# absensi_wemos.net
KiCad netlist of a schematic drawn in EAGLE
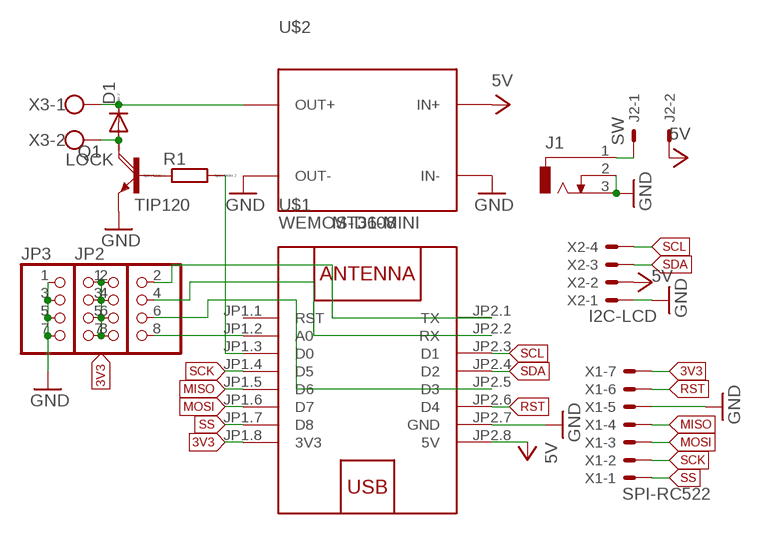
[diagram p0: schematic, sheet 1]

(export (version "E")
  (design (tool "Eeschema 10.0.6"))
  (components
    (comp (ref "D1")
      (value "DIODE-DO-214AC")
      (footprint "eagle-import:DO-214AC")
      (libsource (lib "eagle-import") (part "DIODE-DO-214AC"))
    )
    (comp (ref "J1")
      (value "DCJ0303")
      (footprint "eagle-import:DCJ0303")
      (libsource (lib "eagle-import") (part "DCJ0303"))
    )
    (comp (ref "J2")
      (value "SW")
      (footprint "eagle-import:6410-02")
      (fields (field (name "MF") "MOLEX"))
      (libsource (lib "eagle-import") (part "22-?-0227-2021"))
    )
    (comp (ref "JP2")
      (value "PINHD-2X4")
      (footprint "eagle-import:2X04")
      (libsource (lib "eagle-import") (part "PINHD-2X4"))
    )
    (comp (ref "JP3")
      (value "PINHD-2X4")
      (footprint "eagle-import:2X04")
      (libsource (lib "eagle-import") (part "PINHD-2X4"))
    )
    (comp (ref "Q1")
      (value "TIP120")
      (footprint "eagle-import:TO220AH")
      (libsource (lib "eagle-import") (part "TIP120"))
    )
    (comp (ref "R1")
      (value "R0207/10")
      (footprint "eagle-import:0207_10")
      (libsource (lib "eagle-import") (part "R0207/10"))
    )
    (comp (ref "U$1")
      (value "WEMOS-D1-MINI")
      (footprint "eagle-import:WEMOS-D1-MINI")
      (libsource (lib "eagle-import") (part "WEMOS-D1-MINI"))
    )
    (comp (ref "U$2")
      (value "MT3608")
      (footprint "eagle-import:DC-DC-STEP-UP-MT3608")
      (libsource (lib "eagle-import") (part "DC-DC-STEP-UP-MT3608"))
    )
    (comp (ref "X1")
      (value "SPI-RC522")
      (footprint "eagle-import:6410-07")
      (fields (field (name "MF") "MOLEX"))
      (libsource (lib "eagle-import") (part "22-?-0727-2071"))
    )
    (comp (ref "X2")
      (value "I2C-LCD")
      (footprint "eagle-import:6410-04")
      (fields (field (name "MF") "MOLEX"))
      (libsource (lib "eagle-import") (part "22-?-0427-2041"))
    )
    (comp (ref "X3")
      (value "LOCK")
      (footprint "eagle-import:W237-102")
      (fields (field (name "MPN") "237-102"))
      (libsource (lib "eagle-import") (part "W237-102"))
    )
  )
  (nets
    (net (code "1") (name "3V3") (class "Default")
      (node (ref "JP2") (pin "1") (pinfunction "1_1") (pintype "passive"))
      (node (ref "JP2") (pin "3") (pinfunction "3_3") (pintype "passive"))
      (node (ref "JP2") (pin "5") (pinfunction "5_5") (pintype "passive"))
      (node (ref "JP2") (pin "7") (pinfunction "7_7") (pintype "passive"))
      (node (ref "JP3") (pin "2") (pinfunction "2_2") (pintype "passive"))
      (node (ref "JP3") (pin "4") (pinfunction "4_4") (pintype "passive"))
      (node (ref "JP3") (pin "6") (pinfunction "6_6") (pintype "passive"))
      (node (ref "JP3") (pin "8") (pinfunction "8_8") (pintype "passive"))
      (node (ref "U$1") (pin "JP1.8") (pinfunction "3V3_JP1.8") (pintype "power_in"))
      (node (ref "X1") (pin "7") (pinfunction "S_7") (pintype "passive"))
    )
    (net (code "2") (name "5V") (class "Default")
      (node (ref "J2") (pin "2") (pinfunction "S_2") (pintype "passive"))
      (node (ref "U$1") (pin "JP2.8") (pinfunction "5V_JP2.8") (pintype "power_in"))
      (node (ref "U$2") (pin "IN+") (pinfunction "IN+_IN+") (pintype "bidirectional"))
      (node (ref "X2") (pin "2") (pinfunction "S_2") (pintype "passive"))
    )
    (net (code "3") (name "GND") (class "Default")
      (node (ref "J1") (pin "2") (pinfunction "2_2") (pintype "passive"))
      (node (ref "J1") (pin "3") (pinfunction "3_3") (pintype "passive"))
      (node (ref "JP3") (pin "1") (pinfunction "1_1") (pintype "passive"))
      (node (ref "JP3") (pin "3") (pinfunction "3_3") (pintype "passive"))
      (node (ref "JP3") (pin "5") (pinfunction "5_5") (pintype "passive"))
      (node (ref "JP3") (pin "7") (pinfunction "7_7") (pintype "passive"))
      (node (ref "Q1") (pin "E") (pinfunction "E_E") (pintype "passive"))
      (node (ref "U$1") (pin "JP2.7") (pinfunction "GND_JP2.7") (pintype "power_in"))
      (node (ref "U$2") (pin "IN-") (pinfunction "IN-_IN-") (pintype "bidirectional"))
      (node (ref "U$2") (pin "OUT-") (pinfunction "OUT-_OUT-") (pintype "bidirectional"))
      (node (ref "X1") (pin "5") (pinfunction "S_5") (pintype "passive"))
      (node (ref "X2") (pin "1") (pinfunction "S_1") (pintype "passive"))
    )
    (net (code "4") (name "MISO") (class "Default")
      (node (ref "U$1") (pin "JP1.5") (pinfunction "D6_JP1.5") (pintype "bidirectional"))
      (node (ref "X1") (pin "4") (pinfunction "S_4") (pintype "passive"))
    )
    (net (code "5") (name "MOSI") (class "Default")
      (node (ref "U$1") (pin "JP1.6") (pinfunction "D7_JP1.6") (pintype "bidirectional"))
      (node (ref "X1") (pin "3") (pinfunction "S_3") (pintype "passive"))
    )
    (net (code "6") (name "Net-(J2A-S)") (class "Default")
      (node (ref "J1") (pin "1") (pinfunction "1_1") (pintype "passive"))
      (node (ref "J2") (pin "1") (pinfunction "S_1") (pintype "passive"))
    )
    (net (code "7") (name "Net-(Q1-PadB)") (class "Default")
      (node (ref "Q1") (pin "B") (pinfunction "B_B") (pintype "passive"))
      (node (ref "R1") (pin "1") (pinfunction "1_1") (pintype "passive"))
    )
    (net (code "8") (name "Net-(U$1-A0)") (class "Default")
      (node (ref "JP2") (pin "8") (pinfunction "8_8") (pintype "passive"))
      (node (ref "U$1") (pin "JP1.2") (pinfunction "A0_JP1.2") (pintype "bidirectional"))
    )
    (net (code "9") (name "Net-(U$1-D0)") (class "Default")
      (node (ref "R1") (pin "2") (pinfunction "2_2") (pintype "passive"))
      (node (ref "U$1") (pin "JP1.3") (pinfunction "D0_JP1.3") (pintype "bidirectional"))
    )
    (net (code "10") (name "Net-(U$1-D3)") (class "Default")
      (node (ref "JP2") (pin "6") (pinfunction "6_6") (pintype "passive"))
      (node (ref "U$1") (pin "JP2.5") (pinfunction "D3_JP2.5") (pintype "bidirectional"))
    )
    (net (code "11") (name "Net-(U$1-RX)") (class "Default")
      (node (ref "JP2") (pin "4") (pinfunction "4_4") (pintype "passive"))
      (node (ref "U$1") (pin "JP2.2") (pinfunction "RX_JP2.2") (pintype "bidirectional"))
    )
    (net (code "12") (name "Net-(U$1-TX)") (class "Default")
      (node (ref "JP2") (pin "2") (pinfunction "2_2") (pintype "passive"))
      (node (ref "U$1") (pin "JP2.1") (pinfunction "TX_JP2.1") (pintype "bidirectional"))
    )
    (net (code "13") (name "Net-(X3A-KL)") (class "Default")
      (node (ref "D1") (pin "C") (pinfunction "C_C") (pintype "passive"))
      (node (ref "U$2") (pin "OUT+") (pinfunction "OUT+_OUT+") (pintype "bidirectional"))
      (node (ref "X3") (pin "1") (pinfunction "KL_1") (pintype "passive"))
    )
    (net (code "14") (name "Net-(X3B-KL)") (class "Default")
      (node (ref "D1") (pin "A") (pinfunction "A_A") (pintype "passive"))
      (node (ref "Q1") (pin "C") (pinfunction "C_C") (pintype "passive"))
      (node (ref "X3") (pin "2") (pinfunction "KL_2") (pintype "passive"))
    )
    (net (code "15") (name "RST") (class "Default")
      (node (ref "U$1") (pin "JP2.6") (pinfunction "D4_JP2.6") (pintype "bidirectional"))
      (node (ref "X1") (pin "6") (pinfunction "S_6") (pintype "passive"))
    )
    (net (code "16") (name "SCK") (class "Default")
      (node (ref "U$1") (pin "JP1.4") (pinfunction "D5_JP1.4") (pintype "bidirectional"))
      (node (ref "X1") (pin "2") (pinfunction "S_2") (pintype "passive"))
    )
    (net (code "17") (name "SCL") (class "Default")
      (node (ref "U$1") (pin "JP2.3") (pinfunction "D1_JP2.3") (pintype "bidirectional"))
      (node (ref "X2") (pin "4") (pinfunction "S_4") (pintype "passive"))
    )
    (net (code "18") (name "SDA") (class "Default")
      (node (ref "U$1") (pin "JP2.4") (pinfunction "D2_JP2.4") (pintype "bidirectional"))
      (node (ref "X2") (pin "3") (pinfunction "S_3") (pintype "passive"))
    )
    (net (code "19") (name "SS") (class "Default")
      (node (ref "U$1") (pin "JP1.7") (pinfunction "D8_JP1.7") (pintype "bidirectional"))
      (node (ref "X1") (pin "1") (pinfunction "S_1") (pintype "passive"))
    )
    (net (code "20") (name "unconnected-(U$1-RST-PadJP1.1)") (class "Default")
      (node (ref "U$1") (pin "JP1.1") (pinfunction "RST_JP1.1") (pintype "bidirectional"))
    )
  )
)
